# SunS_Structure_Thermometer.net
KiCad netlist of a schematic drawn in Altium Designer
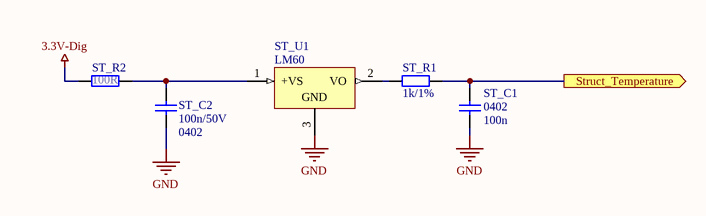
[diagram p0: SunS_Structure_Thermometer.SchDoc]

(export (version "E")
  (design (tool "Eeschema 10.0.6"))
  (components
    (comp (ref "ST_C1")
      (value "0402")
      (footprint "SMD_Capacitor_0402")
      (description "Capacitor")
      (fields (field (name "ALTIUM_VALUE") "100n") (field (name "PUBLISHER") "Altium Limited"))
      (libsource (lib "Miscellaneous Devices") (part "Cap"))
    )
    (comp (ref "ST_C2")
      (value "100n/50V")
      (footprint "SMD_Capacitor_0402")
      (description "Ceramic Cap Kemet COTS 10n/50V X7R 0402")
      (fields
        (field (name "MANUFACTURERPARTNUMBER") "C0402T103K5RALTU")
        (field (name "MANUFACTURER") "Kemet")
        (field (name "PACKAGE") "0402")
      )
      (libsource (lib "capacitors") (part "Cer_C0402T103K5RALTU"))
    )
    (comp (ref "ST_R1")
      (value "1k/1%")
      (footprint "SMD_Resistor_0402")
      (description "1k/1% Vishay CRCW 0402 Resistor. 63mW, 100ppm, 50V.")
      (fields
        (field (name "MANUFACTURER") "Vishay")
        (field (name "MANUFACTURERPARTNUMBER") "CRCW04021K00FKxxxx")
      )
      (libsource (lib "resistors") (part "CRCW04021K00FKxxxx"))
    )
    (comp (ref "ST_R2")
      (value "100R")
      (footprint "SMD_Resistor_0402")
      (description "1k/1% Vishay CRCW 0402 Resistor. 63mW, 100ppm, 50V.")
      (fields
        (field (name "MANUFACTURER") "Vishay")
        (field (name "MANUFACTURERPARTNUMBER") "CRCW04021K00FKxxxx")
      )
      (libsource (lib "resistors") (part "CRCW04021K00FKxxxx"))
    )
    (comp (ref "ST_U1")
      (value "LM60")
      (footprint "SOT23-3")
      (description "Analog temperature sensor")
      (libsource (lib "microcircuits") (part "LM60"))
    )
  )
  (nets
    (net (code "1") (name "/Struct_Temperature") (class "Default")
      (node (ref "ST_C1") (pin "2") (pinfunction "2_2") (pintype "passive"))
      (node (ref "ST_R1") (pin "2") (pinfunction "2_2") (pintype "passive"))
    )
    (net (code "2") (name "3.3V-Dig") (class "Default")
      (node (ref "ST_R2") (pin "1") (pinfunction "1_1") (pintype "passive"))
    )
    (net (code "3") (name "GND") (class "Default")
      (node (ref "ST_C1") (pin "1") (pinfunction "1_1") (pintype "passive"))
      (node (ref "ST_C2") (pin "2") (pinfunction "2_2") (pintype "passive"))
      (node (ref "ST_U1") (pin "3") (pinfunction "GND_3") (pintype "power_in"))
    )
    (net (code "4") (name "Net-(ST_U1-+VS)") (class "Default")
      (node (ref "ST_C2") (pin "1") (pinfunction "1_1") (pintype "passive"))
      (node (ref "ST_R2") (pin "2") (pinfunction "2_2") (pintype "passive"))
      (node (ref "ST_U1") (pin "1") (pinfunction "+VS_1") (pintype "input"))
    )
    (net (code "5") (name "Net-(ST_U1-VO)") (class "Default")
      (node (ref "ST_R1") (pin "1") (pinfunction "1_1") (pintype "passive"))
      (node (ref "ST_U1") (pin "2") (pinfunction "VO_2") (pintype "output"))
    )
  )
)
